# Sheet2.net
KiCad netlist of a schematic drawn in Altium Designer
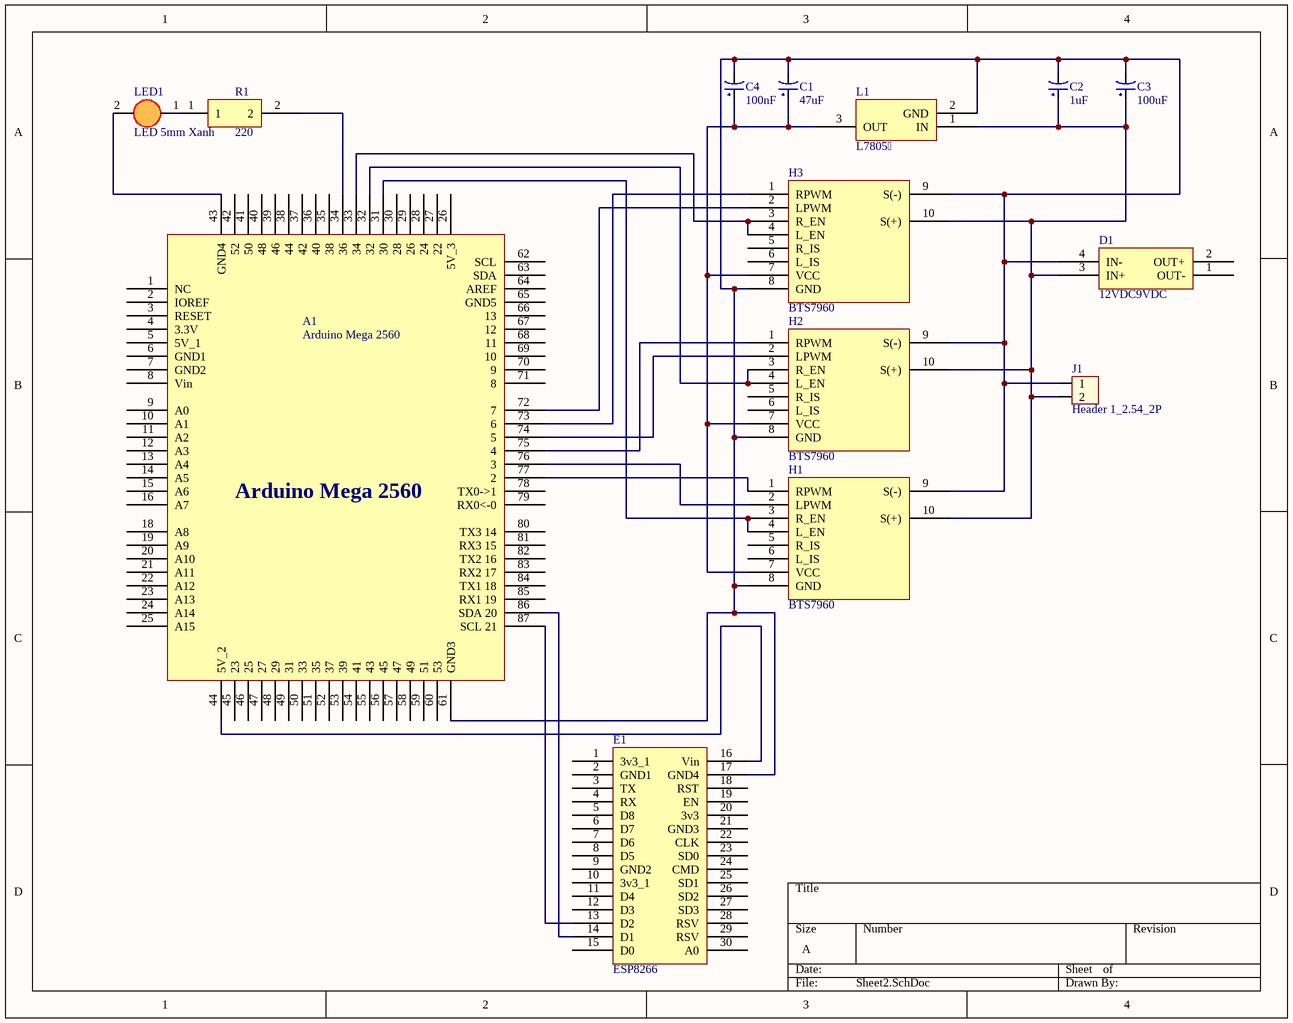
[diagram p0: Sheet2.SchDoc]

(export (version "E")
  (design (tool "Eeschema 10.0.6"))
  (components
    (comp (ref "A1")
      (value "Arduino Mega 2560")
      (footprint "ArduinoMega2560")
      (libsource (lib "ArduinoMega2560") (part "Arduino Mega 2560"))
    )
    (comp (ref "C1")
      (value "47uF")
      (footprint "tu hoa 5mm")
      (description "Cắm")
      (libsource (lib "THU VIEN SCH") (part "Tu Hoa 0.1uF 50V 5x11"))
    )
    (comp (ref "C2")
      (value "1uF")
      (footprint "tu hoa 5mm")
      (description "Cắm")
      (libsource (lib "THU VIEN SCH") (part "Tu Hoa 0.1uF 50V 5x11"))
    )
    (comp (ref "C3")
      (value "100uF")
      (footprint "tu hoa 5mm")
      (description "Cắm")
      (libsource (lib "THU VIEN SCH") (part "Tu Hoa 0.1uF 50V 5x11"))
    )
    (comp (ref "C4")
      (value "100nF")
      (footprint "tu hoa 5mm")
      (description "Cắm")
      (libsource (lib "THU VIEN SCH") (part "Tu Hoa 0.1uF 50V 5x11"))
    )
    (comp (ref "D1")
      (value "12VDC9VDC")
      (footprint "LM2596")
      (libsource (lib "DC_DC_LM2596") (part "Component_1"))
    )
    (comp (ref "E1") (value "ESP8266") (footprint "ESP8266") (libsource (lib "ESP8266") (part "ESP8266")))
    (comp (ref "H1") (value "BTS7960") (footprint "BTS7960") (libsource (lib "BTS7960") (part "BTS7960")))
    (comp (ref "H2") (value "BTS7960") (footprint "BTS7960") (libsource (lib "BTS7960") (part "BTS7960")))
    (comp (ref "H3") (value "BTS7960") (footprint "BTS7960") (libsource (lib "BTS7960") (part "BTS7960")))
    (comp (ref "J1")
      (value "Header 1_2.54_2P")
      (footprint "Header_Duc Cong_2P 2.54")
      (description "12VDC")
      (libsource (lib "THU VIEN SCH") (part "Header 1_2.54_2P"))
    )
    (comp (ref "L1") (value "L7805") (footprint "L7806") (libsource (lib "L7806") (part "Component_1")))
    (comp (ref "LED1")
      (value "LED 5mm Xanh")
      (footprint "LED 5mm Xanh")
      (description "Cắm")
      (libsource (lib "THU VIEN SCH") (part "LED 5mm Xanh"))
    )
    (comp (ref "R1") (value "220") (footprint "Res") (libsource (lib "Res") (part "Component_1")))
  )
  (nets
    (net (code "1") (name "Net-(A1-2)") (class "Default")
      (node (ref "A1") (pin "77") (pinfunction "2_77") (pintype "passive"))
      (node (ref "H1") (pin "1") (pinfunction "RPWM_1") (pintype "passive"))
    )
    (net (code "2") (name "Net-(A1-3)") (class "Default")
      (node (ref "A1") (pin "76") (pinfunction "3_76") (pintype "passive"))
      (node (ref "H1") (pin "2") (pinfunction "LPWM_2") (pintype "passive"))
    )
    (net (code "3") (name "Net-(A1-4)") (class "Default")
      (node (ref "A1") (pin "75") (pinfunction "4_75") (pintype "passive"))
      (node (ref "H2") (pin "1") (pinfunction "RPWM_1") (pintype "passive"))
    )
    (net (code "4") (name "Net-(A1-5)") (class "Default")
      (node (ref "A1") (pin "74") (pinfunction "5_74") (pintype "passive"))
      (node (ref "H2") (pin "2") (pinfunction "LPWM_2") (pintype "passive"))
    )
    (net (code "5") (name "Net-(A1-5V_2)") (class "Default")
      (node (ref "A1") (pin "44") (pinfunction "5V_2_44") (pintype "passive"))
      (node (ref "E1") (pin "16") (pinfunction "Vin_16") (pintype "passive"))
    )
    (net (code "6") (name "Net-(A1-6)") (class "Default")
      (node (ref "A1") (pin "73") (pinfunction "6_73") (pintype "passive"))
      (node (ref "H3") (pin "1") (pinfunction "RPWM_1") (pintype "passive"))
    )
    (net (code "7") (name "Net-(A1-7)") (class "Default")
      (node (ref "A1") (pin "72") (pinfunction "7_72") (pintype "passive"))
      (node (ref "H3") (pin "2") (pinfunction "LPWM_2") (pintype "passive"))
    )
    (net (code "8") (name "Net-(A1-30)") (class "Default")
      (node (ref "A1") (pin "31") (pinfunction "30_31") (pintype "passive"))
      (node (ref "H1") (pin "3") (pinfunction "R_EN_3") (pintype "passive"))
      (node (ref "H1") (pin "4") (pinfunction "L_EN_4") (pintype "passive"))
    )
    (net (code "9") (name "Net-(A1-34)") (class "Default")
      (node (ref "A1") (pin "33") (pinfunction "34_33") (pintype "passive"))
      (node (ref "H3") (pin "3") (pinfunction "R_EN_3") (pintype "passive"))
      (node (ref "H3") (pin "4") (pinfunction "L_EN_4") (pintype "passive"))
    )
    (net (code "10") (name "Net-(A1-36)") (class "Default")
      (node (ref "A1") (pin "34") (pinfunction "36_34") (pintype "passive"))
      (node (ref "R1") (pin "2") (pinfunction "2_2") (pintype "passive"))
    )
    (net (code "11") (name "Net-(A1-GND3)") (class "Default")
      (node (ref "A1") (pin "61") (pinfunction "GND3_61") (pintype "passive"))
      (node (ref "C1") (pin "2") (pinfunction "2_2") (pintype "passive"))
      (node (ref "C2") (pin "2") (pinfunction "2_2") (pintype "passive"))
      (node (ref "C3") (pin "2") (pinfunction "2_2") (pintype "passive"))
      (node (ref "C4") (pin "2") (pinfunction "2_2") (pintype "passive"))
      (node (ref "D1") (pin "4") (pinfunction "IN-_4") (pintype "passive"))
      (node (ref "E1") (pin "17") (pinfunction "GND4_17") (pintype "passive"))
      (node (ref "H1") (pin "8") (pinfunction "GND_8") (pintype "passive"))
      (node (ref "H1") (pin "9") (pinfunction "S(-)_9") (pintype "passive"))
      (node (ref "H2") (pin "8") (pinfunction "GND_8") (pintype "passive"))
      (node (ref "H2") (pin "9") (pinfunction "S(-)_9") (pintype "passive"))
      (node (ref "H3") (pin "8") (pinfunction "GND_8") (pintype "passive"))
      (node (ref "H3") (pin "9") (pinfunction "S(-)_9") (pintype "passive"))
      (node (ref "J1") (pin "1") (pinfunction "1_1") (pintype "passive"))
      (node (ref "L1") (pin "2") (pinfunction "GND_2") (pintype "passive"))
    )
    (net (code "12") (name "Net-(A1-GND4)") (class "Default")
      (node (ref "A1") (pin "43") (pinfunction "GND4_43") (pintype "passive"))
      (node (ref "LED1") (pin "2") (pinfunction "K_2") (pintype "passive"))
    )
    (net (code "13") (name "Net-(A1-SCL_21)") (class "Default")
      (node (ref "A1") (pin "87") (pinfunction "SCL_21_87") (pintype "passive"))
      (node (ref "E1") (pin "13") (pinfunction "D2_13") (pintype "passive"))
    )
    (net (code "14") (name "Net-(A1-SDA_20)") (class "Default")
      (node (ref "A1") (pin "86") (pinfunction "SDA_20_86") (pintype "passive"))
      (node (ref "E1") (pin "14") (pinfunction "D1_14") (pintype "passive"))
    )
    (net (code "15") (name "Net-(D1-IN+)") (class "Default")
      (node (ref "C2") (pin "1") (pinfunction "1_1") (pintype "passive"))
      (node (ref "C3") (pin "1") (pinfunction "1_1") (pintype "passive"))
      (node (ref "D1") (pin "3") (pinfunction "IN+_3") (pintype "passive"))
      (node (ref "H1") (pin "10") (pinfunction "S(+)_10") (pintype "passive"))
      (node (ref "H2") (pin "10") (pinfunction "S(+)_10") (pintype "passive"))
      (node (ref "H3") (pin "10") (pinfunction "S(+)_10") (pintype "passive"))
      (node (ref "J1") (pin "2") (pinfunction "2_2") (pintype "passive"))
      (node (ref "L1") (pin "1") (pinfunction "IN_1") (pintype "passive"))
    )
    (net (code "16") (name "Net-(H1-VCC)") (class "Default")
      (node (ref "C1") (pin "1") (pinfunction "1_1") (pintype "passive"))
      (node (ref "C4") (pin "1") (pinfunction "1_1") (pintype "passive"))
      (node (ref "H1") (pin "7") (pinfunction "VCC_7") (pintype "passive"))
      (node (ref "H2") (pin "7") (pinfunction "VCC_7") (pintype "passive"))
      (node (ref "H3") (pin "7") (pinfunction "VCC_7") (pintype "passive"))
      (node (ref "L1") (pin "3") (pinfunction "OUT_3") (pintype "passive"))
    )
    (net (code "17") (name "Net-(H2-L_EN)") (class "Default")
      (node (ref "A1") (pin "32") (pinfunction "32_32") (pintype "passive"))
      (node (ref "H2") (pin "3") (pinfunction "R_EN_3") (pintype "passive"))
      (node (ref "H2") (pin "4") (pinfunction "L_EN_4") (pintype "passive"))
    )
    (net (code "18") (name "Net-(LED1-A)") (class "Default")
      (node (ref "LED1") (pin "1") (pinfunction "A_1") (pintype "passive"))
      (node (ref "R1") (pin "1") (pinfunction "1_1") (pintype "passive"))
    )
    (net (code "19") (name "unconnected-(A1-3.3V-Pad4)") (class "Default")
      (node (ref "A1") (pin "4") (pinfunction "3.3V_4") (pintype "passive"))
    )
    (net (code "20") (name "unconnected-(A1-5V_1-Pad5)") (class "Default")
      (node (ref "A1") (pin "5") (pinfunction "5V_1_5") (pintype "passive"))
    )
    (net (code "21") (name "unconnected-(A1-5V_3-Pad26)") (class "Default")
      (node (ref "A1") (pin "26") (pinfunction "5V_3_26") (pintype "passive"))
    )
    (net (code "22") (name "unconnected-(A1-8-Pad71)") (class "Default")
      (node (ref "A1") (pin "71") (pinfunction "8_71") (pintype "passive"))
    )
    (net (code "23") (name "unconnected-(A1-9-Pad70)") (class "Default")
      (node (ref "A1") (pin "70") (pinfunction "9_70") (pintype "passive"))
    )
    (net (code "24") (name "unconnected-(A1-10-Pad69)") (class "Default")
      (node (ref "A1") (pin "69") (pinfunction "10_69") (pintype "passive"))
    )
    (net (code "25") (name "unconnected-(A1-11-Pad68)") (class "Default")
      (node (ref "A1") (pin "68") (pinfunction "11_68") (pintype "passive"))
    )
    (net (code "26") (name "unconnected-(A1-12-Pad67)") (class "Default")
      (node (ref "A1") (pin "67") (pinfunction "12_67") (pintype "passive"))
    )
    (net (code "27") (name "unconnected-(A1-13-Pad66)") (class "Default")
      (node (ref "A1") (pin "66") (pinfunction "13_66") (pintype "passive"))
    )
    (net (code "28") (name "unconnected-(A1-22-Pad27)") (class "Default")
      (node (ref "A1") (pin "27") (pinfunction "22_27") (pintype "passive"))
    )
    (net (code "29") (name "unconnected-(A1-23-Pad45)") (class "Default")
      (node (ref "A1") (pin "45") (pinfunction "23_45") (pintype "passive"))
    )
    (net (code "30") (name "unconnected-(A1-24-Pad28)") (class "Default")
      (node (ref "A1") (pin "28") (pinfunction "24_28") (pintype "passive"))
    )
    (net (code "31") (name "unconnected-(A1-25-Pad46)") (class "Default")
      (node (ref "A1") (pin "46") (pinfunction "25_46") (pintype "passive"))
    )
    (net (code "32") (name "unconnected-(A1-26-Pad29)") (class "Default")
      (node (ref "A1") (pin "29") (pinfunction "26_29") (pintype "passive"))
    )
    (net (code "33") (name "unconnected-(A1-27-Pad47)") (class "Default")
      (node (ref "A1") (pin "47") (pinfunction "27_47") (pintype "passive"))
    )
    (net (code "34") (name "unconnected-(A1-28-Pad30)") (class "Default")
      (node (ref "A1") (pin "30") (pinfunction "28_30") (pintype "passive"))
    )
    (net (code "35") (name "unconnected-(A1-29-Pad48)") (class "Default")
      (node (ref "A1") (pin "48") (pinfunction "29_48") (pintype "passive"))
    )
    (net (code "36") (name "unconnected-(A1-31-Pad49)") (class "Default")
      (node (ref "A1") (pin "49") (pinfunction "31_49") (pintype "passive"))
    )
    (net (code "37") (name "unconnected-(A1-33-Pad50)") (class "Default")
      (node (ref "A1") (pin "50") (pinfunction "33_50") (pintype "passive"))
    )
    (net (code "38") (name "unconnected-(A1-35-Pad51)") (class "Default")
      (node (ref "A1") (pin "51") (pinfunction "35_51") (pintype "passive"))
    )
    (net (code "39") (name "unconnected-(A1-37-Pad52)") (class "Default")
      (node (ref "A1") (pin "52") (pinfunction "37_52") (pintype "passive"))
    )
    (net (code "40") (name "unconnected-(A1-38-Pad35)") (class "Default")
      (node (ref "A1") (pin "35") (pinfunction "38_35") (pintype "passive"))
    )
    (net (code "41") (name "unconnected-(A1-39-Pad53)") (class "Default")
      (node (ref "A1") (pin "53") (pinfunction "39_53") (pintype "passive"))
    )
    (net (code "42") (name "unconnected-(A1-40-Pad36)") (class "Default")
      (node (ref "A1") (pin "36") (pinfunction "40_36") (pintype "passive"))
    )
    (net (code "43") (name "unconnected-(A1-41-Pad54)") (class "Default")
      (node (ref "A1") (pin "54") (pinfunction "41_54") (pintype "passive"))
    )
    (net (code "44") (name "unconnected-(A1-42-Pad37)") (class "Default")
      (node (ref "A1") (pin "37") (pinfunction "42_37") (pintype "passive"))
    )
    (net (code "45") (name "unconnected-(A1-43-Pad55)") (class "Default")
      (node (ref "A1") (pin "55") (pinfunction "43_55") (pintype "passive"))
    )
    (net (code "46") (name "unconnected-(A1-44-Pad38)") (class "Default")
      (node (ref "A1") (pin "38") (pinfunction "44_38") (pintype "passive"))
    )
    (net (code "47") (name "unconnected-(A1-45-Pad56)") (class "Default")
      (node (ref "A1") (pin "56") (pinfunction "45_56") (pintype "passive"))
    )
    (net (code "48") (name "unconnected-(A1-46-Pad39)") (class "Default")
      (node (ref "A1") (pin "39") (pinfunction "46_39") (pintype "passive"))
    )
    (net (code "49") (name "unconnected-(A1-47-Pad57)") (class "Default")
      (node (ref "A1") (pin "57") (pinfunction "47_57") (pintype "passive"))
    )
    (net (code "50") (name "unconnected-(A1-48-Pad40)") (class "Default")
      (node (ref "A1") (pin "40") (pinfunction "48_40") (pintype "passive"))
    )
    (net (code "51") (name "unconnected-(A1-49-Pad58)") (class "Default")
      (node (ref "A1") (pin "58") (pinfunction "49_58") (pintype "passive"))
    )
    (net (code "52") (name "unconnected-(A1-50-Pad41)") (class "Default")
      (node (ref "A1") (pin "41") (pinfunction "50_41") (pintype "passive"))
    )
    (net (code "53") (name "unconnected-(A1-51-Pad59)") (class "Default")
      (node (ref "A1") (pin "59") (pinfunction "51_59") (pintype "passive"))
    )
    (net (code "54") (name "unconnected-(A1-52-Pad42)") (class "Default")
      (node (ref "A1") (pin "42") (pinfunction "52_42") (pintype "passive"))
    )
    (net (code "55") (name "unconnected-(A1-53-Pad60)") (class "Default")
      (node (ref "A1") (pin "60") (pinfunction "53_60") (pintype "passive"))
    )
    (net (code "56") (name "unconnected-(A1-A0-Pad9)") (class "Default")
      (node (ref "A1") (pin "9") (pinfunction "A0_9") (pintype "passive"))
    )
    (net (code "57") (name "unconnected-(A1-A1-Pad10)") (class "Default")
      (node (ref "A1") (pin "10") (pinfunction "A1_10") (pintype "passive"))
    )
    (net (code "58") (name "unconnected-(A1-A2-Pad11)") (class "Default")
      (node (ref "A1") (pin "11") (pinfunction "A2_11") (pintype "passive"))
    )
    (net (code "59") (name "unconnected-(A1-A3-Pad12)") (class "Default")
      (node (ref "A1") (pin "12") (pinfunction "A3_12") (pintype "passive"))
    )
    (net (code "60") (name "unconnected-(A1-A4-Pad13)") (class "Default")
      (node (ref "A1") (pin "13") (pinfunction "A4_13") (pintype "passive"))
    )
    (net (code "61") (name "unconnected-(A1-A5-Pad14)") (class "Default")
      (node (ref "A1") (pin "14") (pinfunction "A5_14") (pintype "passive"))
    )
    (net (code "62") (name "unconnected-(A1-A6-Pad15)") (class "Default")
      (node (ref "A1") (pin "15") (pinfunction "A6_15") (pintype "passive"))
    )
    (net (code "63") (name "unconnected-(A1-A7-Pad16)") (class "Default")
      (node (ref "A1") (pin "16") (pinfunction "A7_16") (pintype "passive"))
    )
    (net (code "64") (name "unconnected-(A1-A8-Pad18)") (class "Default")
      (node (ref "A1") (pin "18") (pinfunction "A8_18") (pintype "passive"))
    )
    (net (code "65") (name "unconnected-(A1-A9-Pad19)") (class "Default")
      (node (ref "A1") (pin "19") (pinfunction "A9_19") (pintype "passive"))
    )
    (net (code "66") (name "unconnected-(A1-A10-Pad20)") (class "Default")
      (node (ref "A1") (pin "20") (pinfunction "A10_20") (pintype "passive"))
    )
    (net (code "67") (name "unconnected-(A1-A11-Pad21)") (class "Default")
      (node (ref "A1") (pin "21") (pinfunction "A11_21") (pintype "passive"))
    )
    (net (code "68") (name "unconnected-(A1-A12-Pad22)") (class "Default")
      (node (ref "A1") (pin "22") (pinfunction "A12_22") (pintype "passive"))
    )
    (net (code "69") (name "unconnected-(A1-A13-Pad23)") (class "Default")
      (node (ref "A1") (pin "23") (pinfunction "A13_23") (pintype "passive"))
    )
    (net (code "70") (name "unconnected-(A1-A14-Pad24)") (class "Default")
      (node (ref "A1") (pin "24") (pinfunction "A14_24") (pintype "passive"))
    )
    (net (code "71") (name "unconnected-(A1-A15-Pad25)") (class "Default")
      (node (ref "A1") (pin "25") (pinfunction "A15_25") (pintype "passive"))
    )
    (net (code "72") (name "unconnected-(A1-AREF-Pad64)") (class "Default")
      (node (ref "A1") (pin "64") (pinfunction "AREF_64") (pintype "passive"))
    )
    (net (code "73") (name "unconnected-(A1-GND1-Pad6)") (class "Default")
      (node (ref "A1") (pin "6") (pinfunction "GND1_6") (pintype "passive"))
    )
    (net (code "74") (name "unconnected-(A1-GND2-Pad7)") (class "Default")
      (node (ref "A1") (pin "7") (pinfunction "GND2_7") (pintype "passive"))
    )
    (net (code "75") (name "unconnected-(A1-GND5-Pad65)") (class "Default")
      (node (ref "A1") (pin "65") (pinfunction "GND5_65") (pintype "passive"))
    )
    (net (code "76") (name "unconnected-(A1-IOREF-Pad2)") (class "Default")
      (node (ref "A1") (pin "2") (pinfunction "IOREF_2") (pintype "passive"))
    )
    (net (code "77") (name "unconnected-(A1-NC-Pad1)") (class "Default")
      (node (ref "A1") (pin "1") (pinfunction "NC_1") (pintype "passive"))
    )
    (net (code "78") (name "unconnected-(A1-RESET-Pad3)") (class "Default")
      (node (ref "A1") (pin "3") (pinfunction "RESET_3") (pintype "passive"))
    )
    (net (code "79") (name "unconnected-(A1-RX0<-0-Pad79)") (class "Default")
      (node (ref "A1") (pin "79") (pinfunction "RX0<-0_79") (pintype "passive"))
    )
    (net (code "80") (name "unconnected-(A1-RX1_19-Pad85)") (class "Default")
      (node (ref "A1") (pin "85") (pinfunction "RX1_19_85") (pintype "passive"))
    )
    (net (code "81") (name "unconnected-(A1-RX2_17-Pad83)") (class "Default")
      (node (ref "A1") (pin "83") (pinfunction "RX2_17_83") (pintype "passive"))
    )
    (net (code "82") (name "unconnected-(A1-RX3_15-Pad81)") (class "Default")
      (node (ref "A1") (pin "81") (pinfunction "RX3_15_81") (pintype "passive"))
    )
    (net (code "83") (name "unconnected-(A1-SCL-Pad62)") (class "Default")
      (node (ref "A1") (pin "62") (pinfunction "SCL_62") (pintype "passive"))
    )
    (net (code "84") (name "unconnected-(A1-SDA-Pad63)") (class "Default")
      (node (ref "A1") (pin "63") (pinfunction "SDA_63") (pintype "passive"))
    )
    (net (code "85") (name "unconnected-(A1-TX0->1-Pad78)") (class "Default")
      (node (ref "A1") (pin "78") (pinfunction "TX0->1_78") (pintype "passive"))
    )
    (net (code "86") (name "unconnected-(A1-TX1_18-Pad84)") (class "Default")
      (node (ref "A1") (pin "84") (pinfunction "TX1_18_84") (pintype "passive"))
    )
    (net (code "87") (name "unconnected-(A1-TX2_16-Pad82)") (class "Default")
      (node (ref "A1") (pin "82") (pinfunction "TX2_16_82") (pintype "passive"))
    )
    (net (code "88") (name "unconnected-(A1-TX3_14-Pad80)") (class "Default")
      (node (ref "A1") (pin "80") (pinfunction "TX3_14_80") (pintype "passive"))
    )
    (net (code "89") (name "unconnected-(A1-Vin-Pad8)") (class "Default")
      (node (ref "A1") (pin "8") (pinfunction "Vin_8") (pintype "passive"))
    )
    (net (code "90") (name "unconnected-(D1-OUT+-Pad2)") (class "Default")
      (node (ref "D1") (pin "2") (pinfunction "OUT+_2") (pintype "passive"))
    )
    (net (code "91") (name "unconnected-(D1-OUT--Pad1)") (class "Default")
      (node (ref "D1") (pin "1") (pinfunction "OUT-_1") (pintype "passive"))
    )
    (net (code "92") (name "unconnected-(E1-3v3-Pad20)") (class "Default")
      (node (ref "E1") (pin "20") (pinfunction "3v3_20") (pintype "passive"))
    )
    (net (code "93") (name "unconnected-(E1-3v3_1-Pad1)") (class "Default")
      (node (ref "E1") (pin "1") (pinfunction "3v3_1_1") (pintype "passive"))
    )
    (net (code "94") (name "unconnected-(E1-3v3_1-Pad10)") (class "Default")
      (node (ref "E1") (pin "10") (pinfunction "3v3_1_10") (pintype "passive"))
    )
    (net (code "95") (name "unconnected-(E1-A0-Pad30)") (class "Default")
      (node (ref "E1") (pin "30") (pinfunction "A0_30") (pintype "passive"))
    )
    (net (code "96") (name "unconnected-(E1-CLK-Pad22)") (class "Default")
      (node (ref "E1") (pin "22") (pinfunction "CLK_22") (pintype "passive"))
    )
    (net (code "97") (name "unconnected-(E1-CMD-Pad24)") (class "Default")
      (node (ref "E1") (pin "24") (pinfunction "CMD_24") (pintype "passive"))
    )
    (net (code "98") (name "unconnected-(E1-D0-Pad15)") (class "Default")
      (node (ref "E1") (pin "15") (pinfunction "D0_15") (pintype "passive"))
    )
    (net (code "99") (name "unconnected-(E1-D3-Pad12)") (class "Default")
      (node (ref "E1") (pin "12") (pinfunction "D3_12") (pintype "passive"))
    )
    (net (code "100") (name "unconnected-(E1-D4-Pad11)") (class "Default")
      (node (ref "E1") (pin "11") (pinfunction "D4_11") (pintype "passive"))
    )
    (net (code "101") (name "unconnected-(E1-D5-Pad8)") (class "Default")
      (node (ref "E1") (pin "8") (pinfunction "D5_8") (pintype "passive"))
    )
    (net (code "102") (name "unconnected-(E1-D6-Pad7)") (class "Default")
      (node (ref "E1") (pin "7") (pinfunction "D6_7") (pintype "passive"))
    )
    (net (code "103") (name "unconnected-(E1-D7-Pad6)") (class "Default")
      (node (ref "E1") (pin "6") (pinfunction "D7_6") (pintype "passive"))
    )
    (net (code "104") (name "unconnected-(E1-D8-Pad5)") (class "Default")
      (node (ref "E1") (pin "5") (pinfunction "D8_5") (pintype "passive"))
    )
    (net (code "105") (name "unconnected-(E1-EN-Pad19)") (class "Default")
      (node (ref "E1") (pin "19") (pinfunction "EN_19") (pintype "passive"))
    )
    (net (code "106") (name "unconnected-(E1-GND1-Pad2)") (class "Default")
      (node (ref "E1") (pin "2") (pinfunction "GND1_2") (pintype "passive"))
    )
    (net (code "107") (name "unconnected-(E1-GND2-Pad9)") (class "Default")
      (node (ref "E1") (pin "9") (pinfunction "GND2_9") (pintype "passive"))
    )
    (net (code "108") (name "unconnected-(E1-GND3-Pad21)") (class "Default")
      (node (ref "E1") (pin "21") (pinfunction "GND3_21") (pintype "passive"))
    )
    (net (code "109") (name "unconnected-(E1-RST-Pad18)") (class "Default")
      (node (ref "E1") (pin "18") (pinfunction "RST_18") (pintype "passive"))
    )
    (net (code "110") (name "unconnected-(E1-RSV-Pad28)") (class "Default")
      (node (ref "E1") (pin "28") (pinfunction "RSV_28") (pintype "passive"))
    )
    (net (code "111") (name "unconnected-(E1-RSV-Pad29)") (class "Default")
      (node (ref "E1") (pin "29") (pinfunction "RSV_29") (pintype "passive"))
    )
    (net (code "112") (name "unconnected-(E1-RX-Pad4)") (class "Default")
      (node (ref "E1") (pin "4") (pinfunction "RX_4") (pintype "passive"))
    )
    (net (code "113") (name "unconnected-(E1-SD0-Pad23)") (class "Default")
      (node (ref "E1") (pin "23") (pinfunction "SD0_23") (pintype "passive"))
    )
    (net (code "114") (name "unconnected-(E1-SD1-Pad25)") (class "Default")
      (node (ref "E1") (pin "25") (pinfunction "SD1_25") (pintype "passive"))
    )
    (net (code "115") (name "unconnected-(E1-SD2-Pad26)") (class "Default")
      (node (ref "E1") (pin "26") (pinfunction "SD2_26") (pintype "passive"))
    )
    (net (code "116") (name "unconnected-(E1-SD3-Pad27)") (class "Default")
      (node (ref "E1") (pin "27") (pinfunction "SD3_27") (pintype "passive"))
    )
    (net (code "117") (name "unconnected-(E1-TX-Pad3)") (class "Default")
      (node (ref "E1") (pin "3") (pinfunction "TX_3") (pintype "passive"))
    )
    (net (code "118") (name "unconnected-(H1-L_IS-Pad6)") (class "Default")
      (node (ref "H1") (pin "6") (pinfunction "L_IS_6") (pintype "passive"))
    )
    (net (code "119") (name "unconnected-(H1-R_IS-Pad5)") (class "Default")
      (node (ref "H1") (pin "5") (pinfunction "R_IS_5") (pintype "passive"))
    )
    (net (code "120") (name "unconnected-(H2-L_IS-Pad6)") (class "Default")
      (node (ref "H2") (pin "6") (pinfunction "L_IS_6") (pintype "passive"))
    )
    (net (code "121") (name "unconnected-(H2-R_IS-Pad5)") (class "Default")
      (node (ref "H2") (pin "5") (pinfunction "R_IS_5") (pintype "passive"))
    )
    (net (code "122") (name "unconnected-(H3-L_IS-Pad6)") (class "Default")
      (node (ref "H3") (pin "6") (pinfunction "L_IS_6") (pintype "passive"))
    )
    (net (code "123") (name "unconnected-(H3-R_IS-Pad5)") (class "Default")
      (node (ref "H3") (pin "5") (pinfunction "R_IS_5") (pintype "passive"))
    )
  )
)
